# USB_SCH.net
KiCad netlist of a schematic drawn in Altium Designer
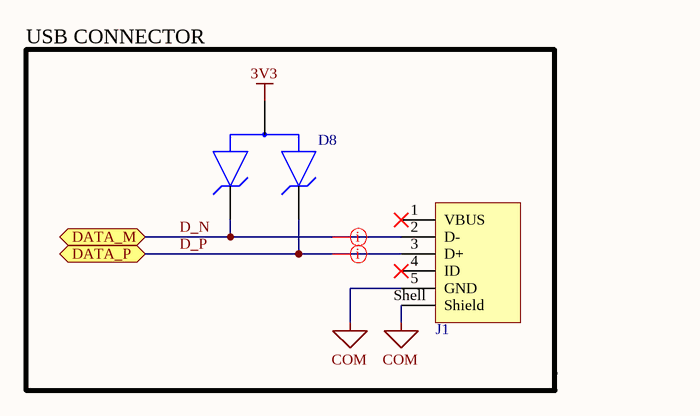
[diagram p0: USB_SCH.SchDoc]

(export (version "E")
  (design (tool "Eeschema 10.0.6"))
  (components
    (comp (ref "D8")
      (value "RCLAMP0502BATCT")
      (footprint "FP-SC75-MFG")
      (description "TVS DIODE 5VWM 25VC SC75")
      (libsource (lib "Altium Content Vault") (part "9603becf907846612ba46a8964e2875"))
    )
    (comp (ref "J1")
      (value "629105150521")
      (footprint "629105150521")
      (description "WR-Micro USB 2.0 Type B, Receptacle, Horizontal, SMT, with Pegs")
      (fields (field (name "MANUFACTURER") "Wurth Elektronik"))
      (libsource (lib "mini-rockets") (part "629105150521"))
    )
  )
  (nets
    (net (code "1") (name "/D_N") (class "Default")
      (node (ref "D8") (pin "2") (pinfunction "2_CATHODE_2") (pintype "passive"))
      (node (ref "J1") (pin "2") (pinfunction "D-_2") (pintype "passive"))
    )
    (net (code "2") (name "/D_P") (class "Default")
      (node (ref "D8") (pin "1") (pinfunction "1_CATHODE_1") (pintype "passive"))
      (node (ref "J1") (pin "3") (pinfunction "D+_3") (pintype "passive"))
    )
    (net (code "3") (name "3V3") (class "Default")
      (node (ref "D8") (pin "3") (pinfunction "COMMON_ANODE_3") (pintype "passive"))
    )
    (net (code "4") (name "COM") (class "Default")
      (node (ref "J1") (pin "5") (pinfunction "GND_5") (pintype "passive"))
      (node (ref "J1") (pin "Shell") (pinfunction "Shield_Shell") (pintype "passive"))
    )
    (net (code "5") (name "unconnected-(J1-ID-Pad4)") (class "Default")
      (node (ref "J1") (pin "4") (pinfunction "ID_4") (pintype "passive+no_connect"))
    )
    (net (code "6") (name "unconnected-(J1-VBUS-Pad1)") (class "Default")
      (node (ref "J1") (pin "1") (pinfunction "VBUS_1") (pintype "passive+no_connect"))
    )
  )
)
